# pcb2.net
KiCad netlist of a schematic drawn in EAGLE
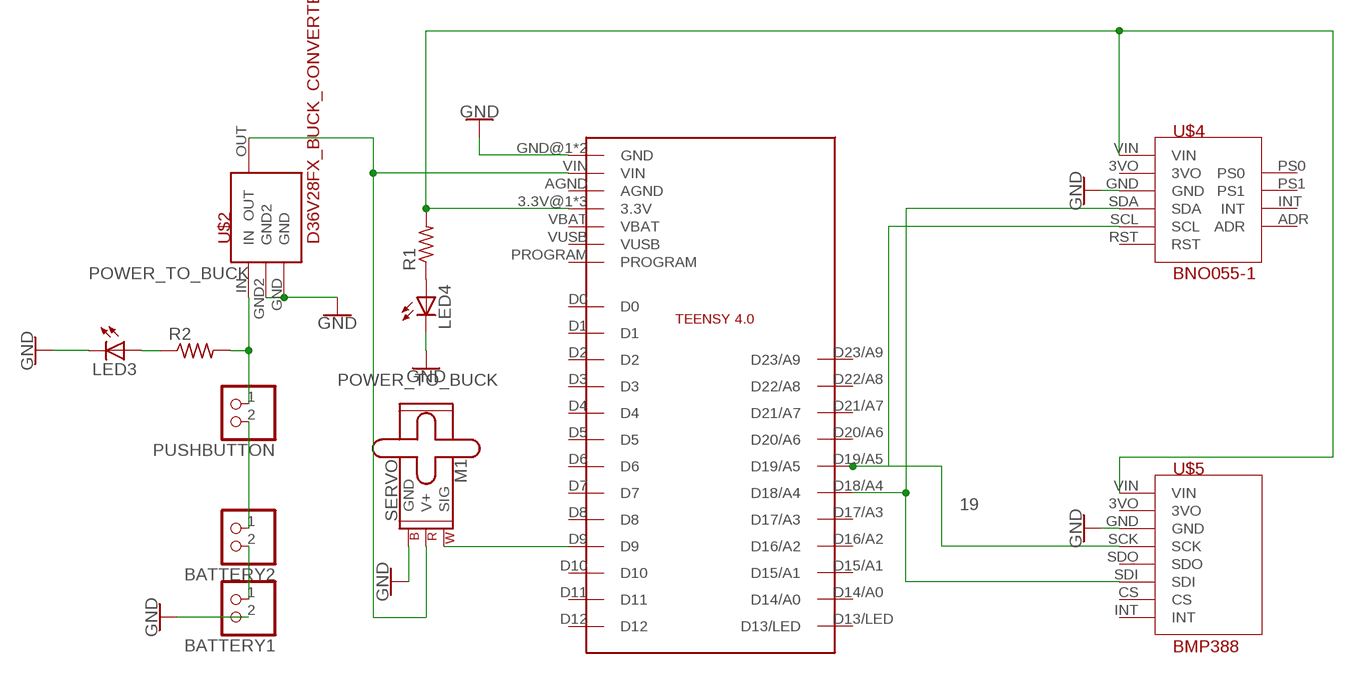
[diagram p0: schematic, sheet 1]

(export (version "E")
  (design (tool "Eeschema 10.0.6"))
  (components
    (comp (ref "BATTERY1")
      (value "JST_2PIN-THM")
      (footprint "eagle-import:JST-PH-2-THM")
      (libsource (lib "eagle-import") (part "JST_2PIN-THM"))
    )
    (comp (ref "BATTERY2")
      (value "JST_2PIN-THM")
      (footprint "eagle-import:JST-PH-2-THM")
      (libsource (lib "eagle-import") (part "JST_2PIN-THM"))
    )
    (comp (ref "LED3")
      (value "LED5MM")
      (footprint "eagle-import:LED5MM")
      (libsource (lib "eagle-import") (part "LED5MM"))
    )
    (comp (ref "LED4")
      (value "LED5MM")
      (footprint "eagle-import:LED5MM")
      (libsource (lib "eagle-import") (part "LED5MM"))
    )
    (comp (ref "M1")
      (value "SERVO")
      (footprint "eagle-import:1X03")
      (libsource (lib "eagle-import") (part "SERVO"))
    )
    (comp (ref "PUSHBUTTON")
      (value "JST_2PIN-THM-RA")
      (footprint "eagle-import:JST-PH-2-THM-RA")
      (libsource (lib "eagle-import") (part "adafruit_420_JST_2PIN-THM-RA"))
    )
    (comp (ref "R1")
      (value "R-US_0207/12")
      (footprint "eagle-import:0207_12")
      (libsource (lib "eagle-import") (part "R-US_0207/12"))
    )
    (comp (ref "R2")
      (value "R-US_0207/12")
      (footprint "eagle-import:0207_12")
      (libsource (lib "eagle-import") (part "R-US_0207/12"))
    )
    (comp (ref "U$1")
      (value "TEENSY4.0")
      (footprint "eagle-import:TEENSY4.0")
      (libsource (lib "eagle-import") (part "TEENSY4.0"))
    )
    (comp (ref "U$2")
      (value "D36V28FX_BUCK_CONVERTER")
      (footprint "eagle-import:D36V28FX_BUCK_CONVERTER")
      (libsource (lib "eagle-import") (part "D36V28FX_BUCK_CONVERTER"))
    )
    (comp (ref "U$4")
      (value "BNO055-1")
      (footprint "eagle-import:BNO055")
      (libsource (lib "eagle-import") (part "BNO055-1"))
    )
    (comp (ref "U$5")
      (value "BMP388")
      (footprint "eagle-import:BMP388")
      (libsource (lib "eagle-import") (part "BMP388"))
    )
  )
  (nets
    (net (code "1") (name "/19") (class "Default")
      (node (ref "U$1") (pin "D19/A5") (pinfunction "D19/A5_D19/A5") (pintype "bidirectional"))
      (node (ref "U$4") (pin "SCL") (pinfunction "SCL_SCL") (pintype "bidirectional"))
      (node (ref "U$5") (pin "SCK") (pinfunction "SCK_SCK") (pintype "bidirectional"))
    )
    (net (code "2") (name "/POWER_TO_BUCK") (class "Default")
      (node (ref "PUSHBUTTON") (pin "1") (pinfunction "2_1") (pintype "passive"))
      (node (ref "R2") (pin "2") (pinfunction "2_2") (pintype "passive"))
      (node (ref "U$2") (pin "IN") (pinfunction "IN_IN") (pintype "bidirectional"))
    )
    (net (code "3") (name "GND") (class "Default")
      (node (ref "BATTERY1") (pin "2") (pinfunction "1_2") (pintype "passive"))
      (node (ref "LED3") (pin "K") (pinfunction "C_K") (pintype "passive"))
      (node (ref "LED4") (pin "K") (pinfunction "C_K") (pintype "passive"))
      (node (ref "M1") (pin "3") (pinfunction "GND_3") (pintype "bidirectional"))
      (node (ref "U$1") (pin "GND@1") (pinfunction "GND_GND@1") (pintype "bidirectional"))
      (node (ref "U$1") (pin "GND@2") (pinfunction "GND_GND@2") (pintype "bidirectional"))
      (node (ref "U$2") (pin "GND") (pinfunction "GND_GND") (pintype "bidirectional"))
      (node (ref "U$2") (pin "GND2") (pinfunction "GND2_GND2") (pintype "bidirectional"))
      (node (ref "U$4") (pin "GND") (pinfunction "GND_GND") (pintype "bidirectional"))
      (node (ref "U$5") (pin "GND") (pinfunction "GND_GND") (pintype "bidirectional"))
    )
    (net (code "4") (name "Net-(BATTERY1-2)") (class "Default")
      (node (ref "BATTERY1") (pin "1") (pinfunction "2_1") (pintype "passive"))
      (node (ref "BATTERY2") (pin "2") (pinfunction "1_2") (pintype "passive"))
    )
    (net (code "5") (name "Net-(BATTERY2-2)") (class "Default")
      (node (ref "BATTERY2") (pin "1") (pinfunction "2_1") (pintype "passive"))
      (node (ref "PUSHBUTTON") (pin "2") (pinfunction "1_2") (pintype "passive"))
    )
    (net (code "6") (name "Net-(LED3-PadA)") (class "Default")
      (node (ref "LED3") (pin "A") (pinfunction "A_A") (pintype "passive"))
      (node (ref "R2") (pin "1") (pinfunction "1_1") (pintype "passive"))
    )
    (net (code "7") (name "Net-(LED4-PadA)") (class "Default")
      (node (ref "LED4") (pin "A") (pinfunction "A_A") (pintype "passive"))
      (node (ref "R1") (pin "1") (pinfunction "1_1") (pintype "passive"))
    )
    (net (code "8") (name "Net-(M1-SIG)") (class "Default")
      (node (ref "M1") (pin "1") (pinfunction "SIG_1") (pintype "bidirectional"))
      (node (ref "U$1") (pin "D9") (pinfunction "D9_D9") (pintype "bidirectional"))
    )
    (net (code "9") (name "Net-(M1-V+)") (class "Default")
      (node (ref "M1") (pin "2") (pinfunction "V+_2") (pintype "bidirectional"))
      (node (ref "U$1") (pin "VIN") (pinfunction "VIN_VIN") (pintype "bidirectional"))
      (node (ref "U$2") (pin "OUT") (pinfunction "OUT_OUT") (pintype "bidirectional"))
    )
    (net (code "10") (name "Net-(R1-Pad2)") (class "Default")
      (node (ref "R1") (pin "2") (pinfunction "2_2") (pintype "passive"))
      (node (ref "U$1") (pin "3.3V@1") (pinfunction "3.3V_3.3V@1") (pintype "bidirectional"))
      (node (ref "U$1") (pin "3.3V@2") (pinfunction "3.3V_3.3V@2") (pintype "bidirectional"))
      (node (ref "U$1") (pin "ON/OFF") (pinfunction "3.3V_ON/OFF") (pintype "bidirectional"))
      (node (ref "U$4") (pin "VIN") (pinfunction "VIN_VIN") (pintype "bidirectional"))
      (node (ref "U$5") (pin "VIN") (pinfunction "VIN_VIN") (pintype "bidirectional"))
    )
    (net (code "11") (name "Net-(U$1-PadD18{slash}A4)") (class "Default")
      (node (ref "U$1") (pin "D18/A4") (pinfunction "D18/A4_D18/A4") (pintype "bidirectional"))
      (node (ref "U$4") (pin "SDA") (pinfunction "SDA_SDA") (pintype "bidirectional"))
      (node (ref "U$5") (pin "SDI") (pinfunction "SDI_SDI") (pintype "bidirectional"))
    )
    (net (code "12") (name "unconnected-(U$1-PadAGND)") (class "Default")
      (node (ref "U$1") (pin "AGND") (pinfunction "AGND_AGND") (pintype "bidirectional"))
    )
    (net (code "13") (name "unconnected-(U$1-PadD0)") (class "Default")
      (node (ref "U$1") (pin "D0") (pinfunction "D0_D0") (pintype "bidirectional"))
    )
    (net (code "14") (name "unconnected-(U$1-PadD1)") (class "Default")
      (node (ref "U$1") (pin "D1") (pinfunction "D1_D1") (pintype "bidirectional"))
    )
    (net (code "15") (name "unconnected-(U$1-PadD2)") (class "Default")
      (node (ref "U$1") (pin "D2") (pinfunction "D2_D2") (pintype "bidirectional"))
    )
    (net (code "16") (name "unconnected-(U$1-PadD3)") (class "Default")
      (node (ref "U$1") (pin "D3") (pinfunction "D3_D3") (pintype "bidirectional"))
    )
    (net (code "17") (name "unconnected-(U$1-PadD4)") (class "Default")
      (node (ref "U$1") (pin "D4") (pinfunction "D4_D4") (pintype "bidirectional"))
    )
    (net (code "18") (name "unconnected-(U$1-PadD5)") (class "Default")
      (node (ref "U$1") (pin "D5") (pinfunction "D5_D5") (pintype "bidirectional"))
    )
    (net (code "19") (name "unconnected-(U$1-PadD6)") (class "Default")
      (node (ref "U$1") (pin "D6") (pinfunction "D6_D6") (pintype "bidirectional"))
    )
    (net (code "20") (name "unconnected-(U$1-PadD7)") (class "Default")
      (node (ref "U$1") (pin "D7") (pinfunction "D7_D7") (pintype "bidirectional"))
    )
    (net (code "21") (name "unconnected-(U$1-PadD8)") (class "Default")
      (node (ref "U$1") (pin "D8") (pinfunction "D8_D8") (pintype "bidirectional"))
    )
    (net (code "22") (name "unconnected-(U$1-PadD10)") (class "Default")
      (node (ref "U$1") (pin "D10") (pinfunction "D10_D10") (pintype "bidirectional"))
    )
    (net (code "23") (name "unconnected-(U$1-PadD11)") (class "Default")
      (node (ref "U$1") (pin "D11") (pinfunction "D11_D11") (pintype "bidirectional"))
    )
    (net (code "24") (name "unconnected-(U$1-PadD12)") (class "Default")
      (node (ref "U$1") (pin "D12") (pinfunction "D12_D12") (pintype "bidirectional"))
    )
    (net (code "25") (name "unconnected-(U$1-PadD13{slash}LED)") (class "Default")
      (node (ref "U$1") (pin "D13/LED") (pinfunction "D13/LED_D13/LED") (pintype "bidirectional"))
    )
    (net (code "26") (name "unconnected-(U$1-PadD14{slash}A0)") (class "Default")
      (node (ref "U$1") (pin "D14/A0") (pinfunction "D14/A0_D14/A0") (pintype "bidirectional"))
    )
    (net (code "27") (name "unconnected-(U$1-PadD15{slash}A1)") (class "Default")
      (node (ref "U$1") (pin "D15/A1") (pinfunction "D15/A1_D15/A1") (pintype "bidirectional"))
    )
    (net (code "28") (name "unconnected-(U$1-PadD16{slash}A2)") (class "Default")
      (node (ref "U$1") (pin "D16/A2") (pinfunction "D16/A2_D16/A2") (pintype "bidirectional"))
    )
    (net (code "29") (name "unconnected-(U$1-PadD17{slash}A3)") (class "Default")
      (node (ref "U$1") (pin "D17/A3") (pinfunction "D17/A3_D17/A3") (pintype "bidirectional"))
    )
    (net (code "30") (name "unconnected-(U$1-PadD20{slash}A6)") (class "Default")
      (node (ref "U$1") (pin "D20/A6") (pinfunction "D20/A6_D20/A6") (pintype "bidirectional"))
    )
    (net (code "31") (name "unconnected-(U$1-PadD21{slash}A7)") (class "Default")
      (node (ref "U$1") (pin "D21/A7") (pinfunction "D21/A7_D21/A7") (pintype "bidirectional"))
    )
    (net (code "32") (name "unconnected-(U$1-PadD22{slash}A8)") (class "Default")
      (node (ref "U$1") (pin "D22/A8") (pinfunction "D22/A8_D22/A8") (pintype "bidirectional"))
    )
    (net (code "33") (name "unconnected-(U$1-PadD23{slash}A9)") (class "Default")
      (node (ref "U$1") (pin "D23/A9") (pinfunction "D23/A9_D23/A9") (pintype "bidirectional"))
    )
    (net (code "34") (name "unconnected-(U$1-PadPROGRAM)") (class "Default")
      (node (ref "U$1") (pin "PROGRAM") (pinfunction "PROGRAM_PROGRAM") (pintype "bidirectional"))
    )
    (net (code "35") (name "unconnected-(U$1-PadVBAT)") (class "Default")
      (node (ref "U$1") (pin "VBAT") (pinfunction "VBAT_VBAT") (pintype "bidirectional"))
    )
    (net (code "36") (name "unconnected-(U$1-PadVUSB)") (class "Default")
      (node (ref "U$1") (pin "VUSB") (pinfunction "VUSB_VUSB") (pintype "bidirectional"))
    )
    (net (code "37") (name "unconnected-(U$4-Pad3VO)") (class "Default")
      (node (ref "U$4") (pin "3VO") (pinfunction "3VO_3VO") (pintype "bidirectional"))
    )
    (net (code "38") (name "unconnected-(U$4-PadADR)") (class "Default")
      (node (ref "U$4") (pin "ADR") (pinfunction "ADR_ADR") (pintype "bidirectional"))
    )
    (net (code "39") (name "unconnected-(U$4-PadINT)") (class "Default")
      (node (ref "U$4") (pin "INT") (pinfunction "INT_INT") (pintype "bidirectional"))
    )
    (net (code "40") (name "unconnected-(U$4-PadPS0)") (class "Default")
      (node (ref "U$4") (pin "PS0") (pinfunction "PS0_PS0") (pintype "bidirectional"))
    )
    (net (code "41") (name "unconnected-(U$4-PadPS1)") (class "Default")
      (node (ref "U$4") (pin "PS1") (pinfunction "PS1_PS1") (pintype "bidirectional"))
    )
    (net (code "42") (name "unconnected-(U$4-PadRST)") (class "Default")
      (node (ref "U$4") (pin "RST") (pinfunction "RST_RST") (pintype "bidirectional"))
    )
    (net (code "43") (name "unconnected-(U$5-Pad3VO)") (class "Default")
      (node (ref "U$5") (pin "3VO") (pinfunction "3VO_3VO") (pintype "bidirectional"))
    )
    (net (code "44") (name "unconnected-(U$5-PadCS)") (class "Default")
      (node (ref "U$5") (pin "CS") (pinfunction "CS_CS") (pintype "bidirectional"))
    )
    (net (code "45") (name "unconnected-(U$5-PadINT)") (class "Default")
      (node (ref "U$5") (pin "INT") (pinfunction "INT_INT") (pintype "bidirectional"))
    )
    (net (code "46") (name "unconnected-(U$5-PadSDO)") (class "Default")
      (node (ref "U$5") (pin "SDO") (pinfunction "SDO_SDO") (pintype "bidirectional"))
    )
  )
)
